# PIC.net
KiCad netlist of a schematic drawn in Altium Designer
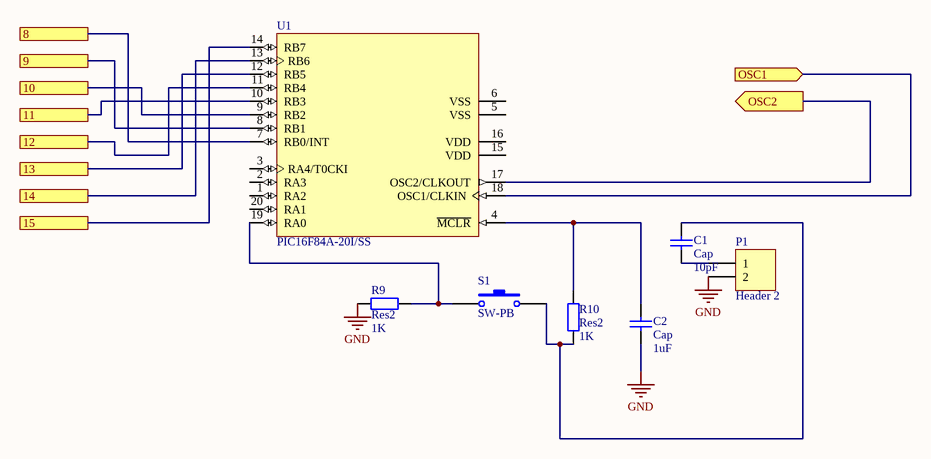
[diagram p0: PIC.SchDoc]

(export (version "E")
  (design (tool "Eeschema 10.0.6"))
  (components
    (comp (ref "C1")
      (value "Cap")
      (footprint "RAD-0.3")
      (description "Capacitor")
      (fields (field (name "ALTIUM_VALUE") "10pF") (field (name "PUBLISHER") "Altium Limited"))
      (libsource (lib "Miscellaneous Devices") (part "Cap"))
    )
    (comp (ref "C2")
      (value "Cap")
      (footprint "RAD-0.3")
      (description "Capacitor")
      (fields (field (name "ALTIUM_VALUE") "1uF") (field (name "PUBLISHER") "Altium Limited"))
      (libsource (lib "Miscellaneous Devices") (part "Cap"))
    )
    (comp (ref "P1")
      (value "Header 2")
      (footprint "HDR1X2")
      (description "Header, 2-Pin")
      (fields (field (name "PUBLISHER") "Altium Limited"))
      (libsource (lib "Miscellaneous Connectors") (part "Header 2"))
    )
    (comp (ref "R9")
      (value "Res2")
      (footprint "AXIAL-0.4")
      (description "Resistor")
      (fields (field (name "ALTIUM_VALUE") "1K") (field (name "PUBLISHER") "Altium Limited"))
      (libsource (lib "Miscellaneous Devices") (part "Res2"))
    )
    (comp (ref "R10")
      (value "Res2")
      (footprint "AXIAL-0.4")
      (description "Resistor")
      (fields (field (name "ALTIUM_VALUE") "1K") (field (name "PUBLISHER") "Altium Limited"))
      (libsource (lib "") (part "Res2_1"))
    )
    (comp (ref "S1")
      (value "SW-PB")
      (footprint "SPST-2")
      (description "Switch")
      (fields (field (name "PUBLISHER") "Altium Limited"))
      (libsource (lib "Miscellaneous Devices") (part "SW-PB"))
    )
    (comp (ref "U1")
      (value "PIC16F84A-20I/SS")
      (footprint "SSOP-SS20_N")
      (fields (field (name "PUBLISHER") "Altium Limited"))
      (libsource (lib "Microchip Microcontroller 8-Bit PIC16") (part "PIC16F84A-20I/SS"))
    )
  )
  (nets
    (net (code "1") (name "/8") (class "Default")
      (node (ref "U1") (pin "7") (pinfunction "RB0/INT_7") (pintype "bidirectional"))
    )
    (net (code "2") (name "/9") (class "Default")
      (node (ref "U1") (pin "8") (pinfunction "RB1_8") (pintype "bidirectional"))
    )
    (net (code "3") (name "/10") (class "Default")
      (node (ref "U1") (pin "9") (pinfunction "RB2_9") (pintype "bidirectional"))
    )
    (net (code "4") (name "/11") (class "Default")
      (node (ref "U1") (pin "10") (pinfunction "RB3_10") (pintype "bidirectional"))
    )
    (net (code "5") (name "/12") (class "Default")
      (node (ref "U1") (pin "11") (pinfunction "RB4_11") (pintype "bidirectional"))
    )
    (net (code "6") (name "/13") (class "Default")
      (node (ref "U1") (pin "12") (pinfunction "RB5_12") (pintype "bidirectional"))
    )
    (net (code "7") (name "/14") (class "Default")
      (node (ref "U1") (pin "13") (pinfunction "RB6_13") (pintype "bidirectional"))
    )
    (net (code "8") (name "/15") (class "Default")
      (node (ref "U1") (pin "14") (pinfunction "RB7_14") (pintype "bidirectional"))
    )
    (net (code "9") (name "/OSC1") (class "Default")
      (node (ref "U1") (pin "18") (pinfunction "OSC1/CLKIN_18") (pintype "input"))
    )
    (net (code "10") (name "/OSC2") (class "Default")
      (node (ref "U1") (pin "17") (pinfunction "OSC2/CLKOUT_17") (pintype "output"))
    )
    (net (code "11") (name "GND") (class "Default")
      (node (ref "C2") (pin "1") (pinfunction "1_1") (pintype "passive"))
      (node (ref "P1") (pin "2") (pinfunction "2_2") (pintype "passive"))
      (node (ref "R9") (pin "1") (pinfunction "1_1") (pintype "passive"))
    )
    (net (code "12") (name "Net-(C1-Pad1)") (class "Default")
      (node (ref "C1") (pin "1") (pinfunction "1_1") (pintype "passive"))
      (node (ref "P1") (pin "1") (pinfunction "1_1") (pintype "passive"))
    )
    (net (code "13") (name "Net-(C1-Pad2)") (class "Default")
      (node (ref "C1") (pin "2") (pinfunction "2_2") (pintype "passive"))
      (node (ref "R10") (pin "1") (pinfunction "1_1") (pintype "passive"))
      (node (ref "S1") (pin "2") (pinfunction "2_2") (pintype "passive"))
    )
    (net (code "14") (name "Net-(U1-RA0)") (class "Default")
      (node (ref "R9") (pin "2") (pinfunction "2_2") (pintype "passive"))
      (node (ref "S1") (pin "1") (pinfunction "1_1") (pintype "passive"))
      (node (ref "U1") (pin "19") (pinfunction "RA0_19") (pintype "bidirectional"))
    )
    (net (code "15") (name "Net-(U1-~{MCLR})") (class "Default")
      (node (ref "C2") (pin "2") (pinfunction "2_2") (pintype "passive"))
      (node (ref "R10") (pin "2") (pinfunction "2_2") (pintype "passive"))
      (node (ref "U1") (pin "4") (pinfunction "~{MCLR}_4") (pintype "input"))
    )
    (net (code "16") (name "unconnected-(U1-RA1-Pad20)") (class "Default")
      (node (ref "U1") (pin "20") (pinfunction "RA1_20") (pintype "bidirectional"))
    )
    (net (code "17") (name "unconnected-(U1-RA2-Pad1)") (class "Default")
      (node (ref "U1") (pin "1") (pinfunction "RA2_1") (pintype "bidirectional"))
    )
    (net (code "18") (name "unconnected-(U1-RA3-Pad2)") (class "Default")
      (node (ref "U1") (pin "2") (pinfunction "RA3_2") (pintype "bidirectional"))
    )
    (net (code "19") (name "unconnected-(U1-RA4{slash}T0CKI-Pad3)") (class "Default")
      (node (ref "U1") (pin "3") (pinfunction "RA4/T0CKI_3") (pintype "bidirectional"))
    )
    (net (code "20") (name "unconnected-(U1-VDD-Pad15)") (class "Default")
      (node (ref "U1") (pin "15") (pinfunction "VDD_15") (pintype "power_in"))
    )
    (net (code "21") (name "unconnected-(U1-VDD-Pad16)") (class "Default")
      (node (ref "U1") (pin "16") (pinfunction "VDD_16") (pintype "power_in"))
    )
    (net (code "22") (name "unconnected-(U1-VSS-Pad5)") (class "Default")
      (node (ref "U1") (pin "5") (pinfunction "VSS_5") (pintype "power_in"))
    )
    (net (code "23") (name "unconnected-(U1-VSS-Pad6)") (class "Default")
      (node (ref "U1") (pin "6") (pinfunction "VSS_6") (pintype "power_in"))
    )
  )
)
